# SCH_Genie-V1_2024-08-10.net
KiCad netlist of a schematic drawn in EasyEDA
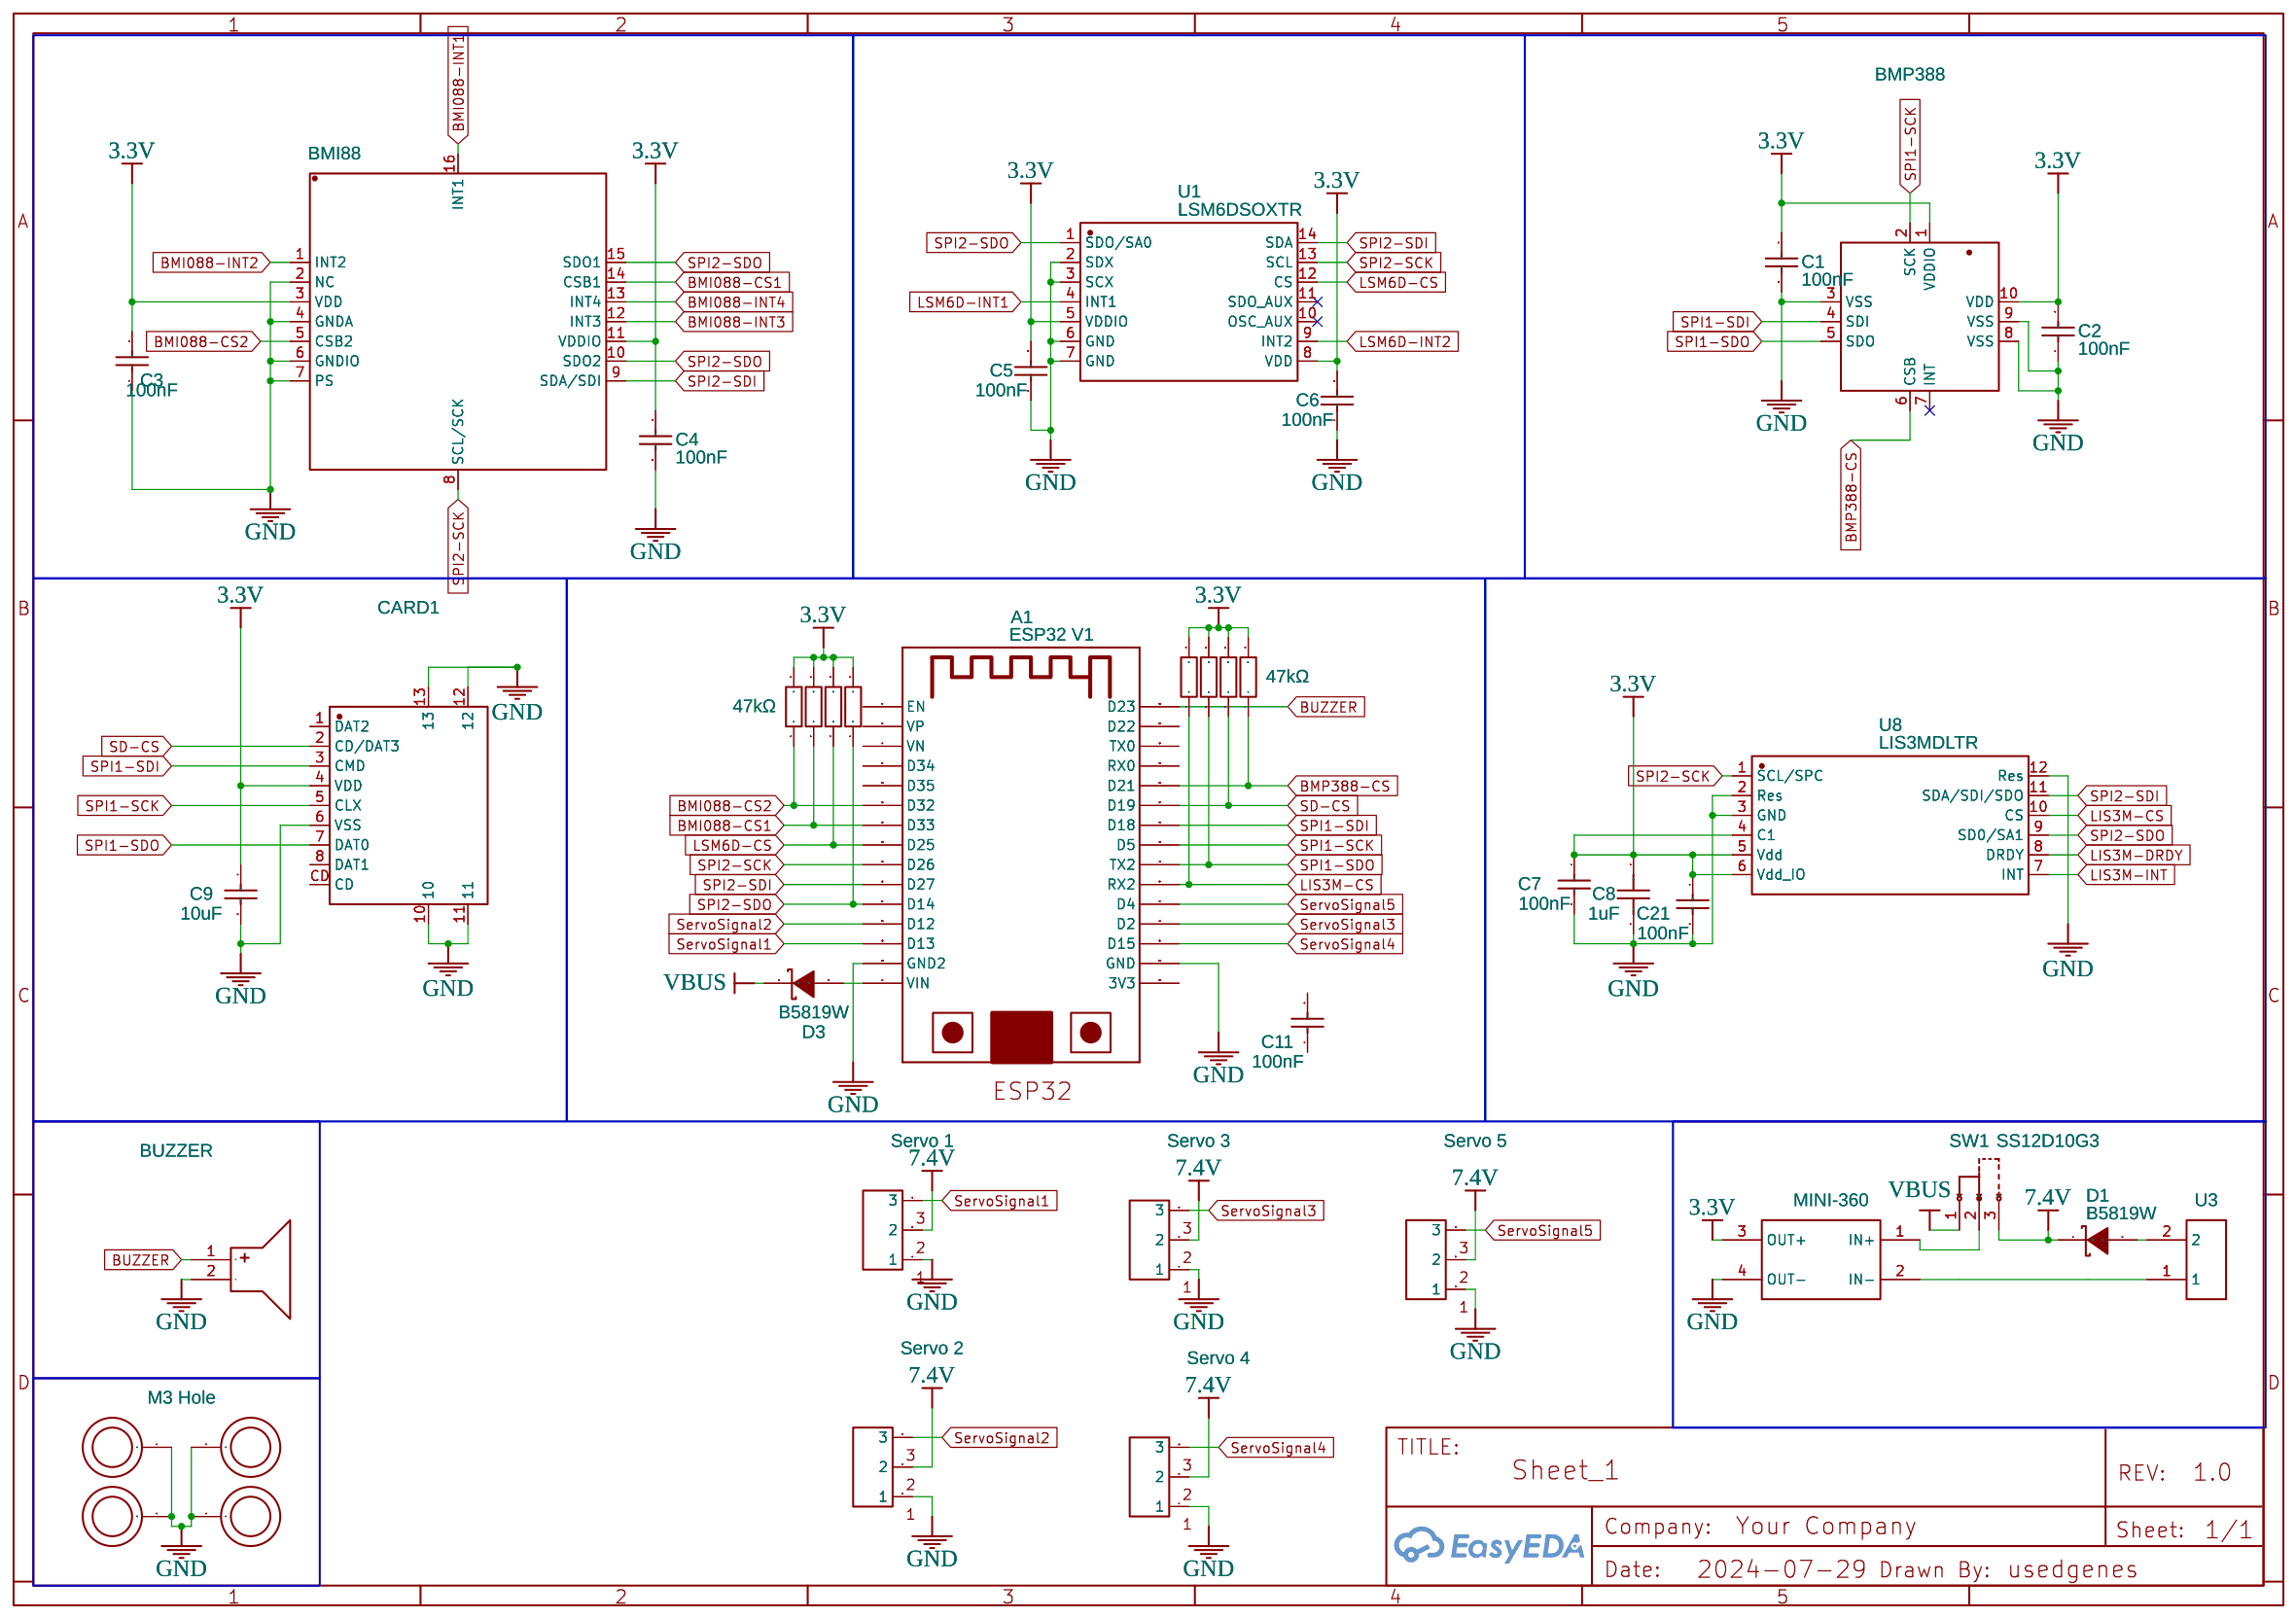
[diagram p0: schematic sheet]

(export (version "E")
  (design (tool "Eeschema 10.0.6"))
  (components
    (comp (ref "A1") (value "ESP32 V1") (libsource (lib "") (part "ESP32-DEVKIT-V1-30PIN")))
    (comp (ref "BMI88")
      (value "BMI088")
      (fields (field (name "Manufacturer") "Bosch(博世)"))
      (libsource (lib "") (part "BMI088"))
    )
    (comp (ref "BMP388")
      (value "BMP388")
      (fields (field (name "Manufacturer") "Bosch(博世)"))
      (libsource (lib "") (part "BMP388"))
    )
    (comp (ref "BUZZER")
      (value "4000Hz")
      (fields
        (field (name "Manufacturer Part") "SKY-1475-0540-45P7.6")
        (field (name "Manufacturer") "S&S(海旭)")
      )
      (libsource (lib "") (part "SKY-1475-0540-45P7.6"))
    )
    (comp (ref "C1")
      (value "100nF")
      (fields
        (field (name "Manufacturer Part") "CL05B104KO5NNNC")
        (field (name "Manufacturer") "SAMSUNG(三星)")
      )
      (libsource (lib "") (part "CL05B104KO5NNNC_1"))
    )
    (comp (ref "C2")
      (value "100nF")
      (fields
        (field (name "Manufacturer Part") "CL05B104KO5NNNC")
        (field (name "Manufacturer") "SAMSUNG(三星)")
      )
      (libsource (lib "") (part "CL05B104KO5NNNC_1"))
    )
    (comp (ref "C3")
      (value "100nF")
      (fields
        (field (name "Manufacturer Part") "CL05B104KO5NNNC")
        (field (name "Manufacturer") "SAMSUNG(三星)")
      )
      (libsource (lib "") (part "CL05B104KO5NNNC_1"))
    )
    (comp (ref "C4")
      (value "100nF")
      (fields
        (field (name "Manufacturer Part") "CL05B104KO5NNNC")
        (field (name "Manufacturer") "SAMSUNG(三星)")
      )
      (libsource (lib "") (part "CL05B104KO5NNNC_1"))
    )
    (comp (ref "C5")
      (value "100nF")
      (fields
        (field (name "Manufacturer Part") "CL05B104KO5NNNC")
        (field (name "Manufacturer") "SAMSUNG(三星)")
      )
      (libsource (lib "") (part "CL05B104KO5NNNC_1"))
    )
    (comp (ref "C6")
      (value "100nF")
      (fields
        (field (name "Manufacturer Part") "CL05B104KO5NNNC")
        (field (name "Manufacturer") "SAMSUNG(三星)")
      )
      (libsource (lib "") (part "CL05B104KO5NNNC_1"))
    )
    (comp (ref "C7")
      (value "100nF")
      (fields
        (field (name "Manufacturer Part") "CL05B104KO5NNNC")
        (field (name "Manufacturer") "SAMSUNG(三星)")
      )
      (libsource (lib "") (part "CL05B104KO5NNNC"))
    )
    (comp (ref "C8")
      (value "1uF")
      (fields
        (field (name "Manufacturer Part") "CL05A105KA5NQNC")
        (field (name "Manufacturer") "SAMSUNG(三星)")
      )
      (libsource (lib "") (part "CL05A105KA5NQNC"))
    )
    (comp (ref "C9")
      (value "10uF")
      (fields
        (field (name "Manufacturer Part") "CL05A106MQ5NUNC")
        (field (name "Manufacturer") "SAMSUNG(三星)")
      )
      (libsource (lib "") (part "CL05A106MQ5NUNC"))
    )
    (comp (ref "C11")
      (value "100nF")
      (fields
        (field (name "Manufacturer Part") "CL05B104KO5NNNC")
        (field (name "Manufacturer") "SAMSUNG(三星)")
      )
      (libsource (lib "") (part "CL05B104KO5NNNC_1"))
    )
    (comp (ref "C21")
      (value "100nF")
      (fields
        (field (name "Manufacturer Part") "CL05B104KO5NNNC")
        (field (name "Manufacturer") "SAMSUNG(三星)")
      )
      (libsource (lib "") (part "CL05B104KO5NNNC"))
    )
    (comp (ref "CARD1")
      (value "TF PUSH")
      (fields (field (name "Manufacturer") "SHOU HAN(首韩)"))
      (libsource (lib "") (part "TF PUSH"))
    )
    (comp (ref "D1")
      (value "B5819W")
      (fields (field (name "Manufacturer") "MDD(辰达半导体)"))
      (libsource (lib "") (part "B5819W"))
    )
    (comp (ref "D3")
      (value "B5819W")
      (fields (field (name "Manufacturer") "MDD(辰达半导体)"))
      (libsource (lib "") (part "B5819W"))
    )
    (comp (ref "H1") (value "M3 Hole") (libsource (lib "") (part "3MM_HOLE_1")))
    (comp (ref "H2") (value "3MM_HOLE") (libsource (lib "") (part "3MM_HOLE")))
    (comp (ref "H3") (value "3MM_HOLE") (libsource (lib "") (part "3MM_HOLE_1")))
    (comp (ref "H4") (value "3MM_HOLE") (libsource (lib "") (part "3MM_HOLE")))
    (comp (ref "MINI-360") (value "MINI-360") (libsource (lib "") (part "MINI-360")))
    (comp (ref "P1")
      (value "Servo 2")
      (fields
        (field (name "Manufacturer Part") "Female headerHDR1X8-2.54")
        (field (name "Manufacturer") "BOOMELE")
      )
      (libsource (lib "") (part "HEADER PAD 3X RMM COPY"))
    )
    (comp (ref "P2")
      (value "Servo 1")
      (fields
        (field (name "Manufacturer Part") "Female headerHDR1X8-2.54")
        (field (name "Manufacturer") "BOOMELE")
      )
      (libsource (lib "") (part "HEADER PAD 3X RMM COPY"))
    )
    (comp (ref "P3")
      (value "Servo 3")
      (fields
        (field (name "Manufacturer Part") "Female headerHDR1X8-2.54")
        (field (name "Manufacturer") "BOOMELE")
      )
      (libsource (lib "") (part "HEADER PAD 3X RMM COPY"))
    )
    (comp (ref "P4")
      (value "Servo 5")
      (fields
        (field (name "Manufacturer Part") "Female headerHDR1X8-2.54")
        (field (name "Manufacturer") "BOOMELE")
      )
      (libsource (lib "") (part "HEADER PAD 3X RMM COPY"))
    )
    (comp (ref "P5")
      (value "Servo 4")
      (fields
        (field (name "Manufacturer Part") "Female headerHDR1X8-2.54")
        (field (name "Manufacturer") "BOOMELE")
      )
      (libsource (lib "") (part "HEADER PAD 3X RMM COPY"))
    )
    (comp (ref "R1")
      (value "47kΩ")
      (fields
        (field (name "Manufacturer Part") "0402WGF4702TCE")
        (field (name "Manufacturer") "UNI-ROYAL(厚声)")
      )
      (libsource (lib "") (part "0402WGF4702TCE"))
    )
    (comp (ref "R2")
      (value "47kΩ")
      (fields
        (field (name "Manufacturer Part") "0402WGF4702TCE")
        (field (name "Manufacturer") "UNI-ROYAL(厚声)")
      )
      (libsource (lib "") (part "0402WGF4702TCE"))
    )
    (comp (ref "R3")
      (value "47kΩ")
      (fields
        (field (name "Manufacturer Part") "0402WGF4702TCE")
        (field (name "Manufacturer") "UNI-ROYAL(厚声)")
      )
      (libsource (lib "") (part "0402WGF4702TCE"))
    )
    (comp (ref "R4")
      (value "47kΩ")
      (fields
        (field (name "Manufacturer Part") "0402WGF4702TCE")
        (field (name "Manufacturer") "UNI-ROYAL(厚声)")
      )
      (libsource (lib "") (part "0402WGF4702TCE"))
    )
    (comp (ref "R5")
      (value "47kΩ")
      (fields
        (field (name "Manufacturer Part") "0402WGF4702TCE")
        (field (name "Manufacturer") "UNI-ROYAL(厚声)")
      )
      (libsource (lib "") (part "0402WGF4702TCE"))
    )
    (comp (ref "R7")
      (value "47kΩ")
      (fields
        (field (name "Manufacturer Part") "0402WGF4702TCE")
        (field (name "Manufacturer") "UNI-ROYAL(厚声)")
      )
      (libsource (lib "") (part "0402WGF4702TCE"))
    )
    (comp (ref "R8")
      (value "47kΩ")
      (fields
        (field (name "Manufacturer Part") "0402WGF4702TCE")
        (field (name "Manufacturer") "UNI-ROYAL(厚声)")
      )
      (libsource (lib "") (part "0402WGF4702TCE"))
    )
    (comp (ref "R9")
      (value "47kΩ")
      (fields
        (field (name "Manufacturer Part") "0402WGF4702TCE")
        (field (name "Manufacturer") "UNI-ROYAL(厚声)")
      )
      (libsource (lib "") (part "0402WGF4702TCE"))
    )
    (comp (ref "SW1")
      (value "SS12D10G3")
      (fields (field (name "Manufacturer") "SHOU HAN(首韩)"))
      (libsource (lib "") (part "SS12D10G3"))
    )
    (comp (ref "U1")
      (value "LSM6DSOXTR")
      (fields (field (name "Manufacturer") "ST(意法半导体)"))
      (libsource (lib "") (part "LSM6DSOXTR"))
    )
    (comp (ref "U3") (value "Power Pins") (libsource (lib "") (part "1X2")))
    (comp (ref "U8")
      (value "LIS3MDLTR")
      (fields (field (name "Manufacturer") "ST(意法半导体)"))
      (libsource (lib "") (part "LIS3MDLTR"))
    )
  )
  (nets
    (net (code "1") (name "3.3V") (class "Default")
      (node (ref "BMI88") (pin "11") (pinfunction "VDDIO_11") (pintype "unspecified"))
      (node (ref "BMI88") (pin "3") (pinfunction "VDD_3") (pintype "unspecified"))
      (node (ref "BMP388") (pin "1") (pinfunction "VDDIO_1") (pintype "unspecified"))
      (node (ref "BMP388") (pin "10") (pinfunction "VDD_10") (pintype "unspecified"))
      (node (ref "C1") (pin "2") (pinfunction "2_2") (pintype "input"))
      (node (ref "C2") (pin "2") (pinfunction "2_2") (pintype "input"))
      (node (ref "C21") (pin "1") (pinfunction "1_1") (pintype "input"))
      (node (ref "C3") (pin "2") (pinfunction "2_2") (pintype "input"))
      (node (ref "C4") (pin "2") (pinfunction "2_2") (pintype "input"))
      (node (ref "C5") (pin "2") (pinfunction "2_2") (pintype "input"))
      (node (ref "C6") (pin "2") (pinfunction "2_2") (pintype "input"))
      (node (ref "C7") (pin "1") (pinfunction "1_1") (pintype "input"))
      (node (ref "C8") (pin "2") (pinfunction "2_2") (pintype "unspecified"))
      (node (ref "C9") (pin "1") (pinfunction "1_1") (pintype "input"))
      (node (ref "CARD1") (pin "4") (pinfunction "VDD_4") (pintype "unspecified"))
      (node (ref "MINI-360") (pin "3") (pinfunction "OUT+_3") (pintype "unspecified"))
      (node (ref "R1") (pin "2") (pinfunction "2_2") (pintype "input"))
      (node (ref "R2") (pin "2") (pinfunction "2_2") (pintype "input"))
      (node (ref "R3") (pin "2") (pinfunction "2_2") (pintype "input"))
      (node (ref "R4") (pin "2") (pinfunction "2_2") (pintype "input"))
      (node (ref "R5") (pin "2") (pinfunction "2_2") (pintype "input"))
      (node (ref "R7") (pin "2") (pinfunction "2_2") (pintype "input"))
      (node (ref "R8") (pin "2") (pinfunction "2_2") (pintype "input"))
      (node (ref "R9") (pin "2") (pinfunction "2_2") (pintype "input"))
      (node (ref "U1") (pin "5") (pinfunction "VDDIO_5") (pintype "unspecified"))
      (node (ref "U1") (pin "8") (pinfunction "VDD_8") (pintype "unspecified"))
      (node (ref "U8") (pin "4") (pinfunction "C1_4") (pintype "unspecified"))
      (node (ref "U8") (pin "5") (pinfunction "Vdd_5") (pintype "unspecified"))
      (node (ref "U8") (pin "6") (pinfunction "Vdd_IO_6") (pintype "unspecified"))
    )
    (net (code "2") (name "7.4V") (class "Default")
      (node (ref "D1") (pin "1") (pinfunction "K_1") (pintype "unspecified"))
      (node (ref "P1") (pin "2") (pinfunction "2_2") (pintype "unspecified"))
      (node (ref "P2") (pin "2") (pinfunction "2_2") (pintype "unspecified"))
      (node (ref "P3") (pin "2") (pinfunction "2_2") (pintype "unspecified"))
      (node (ref "P4") (pin "2") (pinfunction "2_2") (pintype "unspecified"))
      (node (ref "P5") (pin "2") (pinfunction "2_2") (pintype "unspecified"))
      (node (ref "SW1") (pin "3") (pinfunction "3_3") (pintype "unspecified"))
    )
    (net (code "3") (name "BMI088-CS1") (class "Default")
      (node (ref "A1") (pin "D33") (pinfunction "D33_D33") (pintype "unspecified"))
      (node (ref "BMI88") (pin "14") (pinfunction "CSB1_14") (pintype "unspecified"))
      (node (ref "R1") (pin "1") (pinfunction "1_1") (pintype "input"))
    )
    (net (code "4") (name "BMI088-CS2") (class "Default")
      (node (ref "A1") (pin "D32") (pinfunction "D32_D32") (pintype "unspecified"))
      (node (ref "BMI88") (pin "5") (pinfunction "CSB2_5") (pintype "unspecified"))
      (node (ref "R4") (pin "1") (pinfunction "1_1") (pintype "input"))
    )
    (net (code "5") (name "BMI088-INT1") (class "Default")
      (node (ref "BMI88") (pin "16") (pinfunction "INT1_16") (pintype "unspecified"))
    )
    (net (code "6") (name "BMI088-INT2") (class "Default")
      (node (ref "BMI88") (pin "1") (pinfunction "INT2_1") (pintype "unspecified"))
    )
    (net (code "7") (name "BMI088-INT3") (class "Default")
      (node (ref "BMI88") (pin "12") (pinfunction "INT3_12") (pintype "unspecified"))
    )
    (net (code "8") (name "BMI088-INT4") (class "Default")
      (node (ref "BMI88") (pin "13") (pinfunction "INT4_13") (pintype "unspecified"))
    )
    (net (code "9") (name "BMP388-CS") (class "Default")
      (node (ref "A1") (pin "D21") (pinfunction "D21_D21") (pintype "unspecified"))
      (node (ref "BMP388") (pin "6") (pinfunction "CSB_6") (pintype "unspecified"))
      (node (ref "R5") (pin "1") (pinfunction "1_1") (pintype "input"))
    )
    (net (code "10") (name "BUZZER") (class "Default")
      (node (ref "A1") (pin "D23") (pinfunction "D23_D23") (pintype "unspecified"))
      (node (ref "BUZZER") (pin "1") (pinfunction "+_1") (pintype "unspecified"))
    )
    (net (code "11") (name "GND") (class "Default")
      (node (ref "A1") (pin "GND") (pinfunction "GND_GND") (pintype "unspecified"))
      (node (ref "A1") (pin "GND2") (pinfunction "GND2_GND2") (pintype "unspecified"))
      (node (ref "BMI88") (pin "2") (pinfunction "NC_2") (pintype "unspecified"))
      (node (ref "BMI88") (pin "4") (pinfunction "GNDA_4") (pintype "unspecified"))
      (node (ref "BMI88") (pin "6") (pinfunction "GNDIO_6") (pintype "unspecified"))
      (node (ref "BMI88") (pin "7") (pinfunction "PS_7") (pintype "unspecified"))
      (node (ref "BMP388") (pin "3") (pinfunction "VSS_3") (pintype "unspecified"))
      (node (ref "BMP388") (pin "8") (pinfunction "VSS_8") (pintype "unspecified"))
      (node (ref "BMP388") (pin "9") (pinfunction "VSS_9") (pintype "unspecified"))
      (node (ref "BUZZER") (pin "2") (pinfunction "-_2") (pintype "unspecified"))
      (node (ref "C1") (pin "1") (pinfunction "1_1") (pintype "input"))
      (node (ref "C2") (pin "1") (pinfunction "1_1") (pintype "input"))
      (node (ref "C21") (pin "2") (pinfunction "2_2") (pintype "input"))
      (node (ref "C3") (pin "1") (pinfunction "1_1") (pintype "input"))
      (node (ref "C4") (pin "1") (pinfunction "1_1") (pintype "input"))
      (node (ref "C5") (pin "1") (pinfunction "1_1") (pintype "input"))
      (node (ref "C6") (pin "1") (pinfunction "1_1") (pintype "input"))
      (node (ref "C7") (pin "2") (pinfunction "2_2") (pintype "input"))
      (node (ref "C8") (pin "1") (pinfunction "1_1") (pintype "unspecified"))
      (node (ref "C9") (pin "2") (pinfunction "2_2") (pintype "input"))
      (node (ref "CARD1") (pin "10") (pinfunction "10_10") (pintype "unspecified"))
      (node (ref "CARD1") (pin "11") (pinfunction "11_11") (pintype "unspecified"))
      (node (ref "CARD1") (pin "12") (pinfunction "12_12") (pintype "unspecified"))
      (node (ref "CARD1") (pin "13") (pinfunction "13_13") (pintype "unspecified"))
      (node (ref "CARD1") (pin "6") (pinfunction "VSS_6") (pintype "unspecified"))
      (node (ref "H1") (pin "1") (pinfunction "1_1") (pintype "bidirectional"))
      (node (ref "H2") (pin "1") (pinfunction "1_1") (pintype "bidirectional"))
      (node (ref "H3") (pin "1") (pinfunction "1_1") (pintype "bidirectional"))
      (node (ref "H4") (pin "1") (pinfunction "1_1") (pintype "bidirectional"))
      (node (ref "MINI-360") (pin "4") (pinfunction "OUT-_4") (pintype "unspecified"))
      (node (ref "P1") (pin "1") (pinfunction "1_1") (pintype "unspecified"))
      (node (ref "P2") (pin "1") (pinfunction "1_1") (pintype "unspecified"))
      (node (ref "P3") (pin "1") (pinfunction "1_1") (pintype "unspecified"))
      (node (ref "P4") (pin "1") (pinfunction "1_1") (pintype "unspecified"))
      (node (ref "P5") (pin "1") (pinfunction "1_1") (pintype "unspecified"))
      (node (ref "U1") (pin "2") (pinfunction "SDX_2") (pintype "unspecified"))
      (node (ref "U1") (pin "3") (pinfunction "SCX_3") (pintype "unspecified"))
      (node (ref "U1") (pin "6") (pinfunction "GND_6") (pintype "unspecified"))
      (node (ref "U1") (pin "7") (pinfunction "GND_7") (pintype "unspecified"))
      (node (ref "U8") (pin "12") (pinfunction "Res_12") (pintype "unspecified"))
      (node (ref "U8") (pin "2") (pinfunction "Res_2") (pintype "unspecified"))
      (node (ref "U8") (pin "3") (pinfunction "GND_3") (pintype "unspecified"))
    )
    (net (code "12") (name "LIS3M-CS") (class "Default")
      (node (ref "A1") (pin "RX2") (pinfunction "RX2_RX2") (pintype "unspecified"))
      (node (ref "R8") (pin "1") (pinfunction "1_1") (pintype "input"))
      (node (ref "U8") (pin "10") (pinfunction "CS_10") (pintype "unspecified"))
    )
    (net (code "13") (name "LIS3M-DRDY") (class "Default")
      (node (ref "U8") (pin "8") (pinfunction "DRDY_8") (pintype "unspecified"))
    )
    (net (code "14") (name "LIS3M-INT") (class "Default")
      (node (ref "U8") (pin "7") (pinfunction "INT_7") (pintype "unspecified"))
    )
    (net (code "15") (name "LSM6D-CS") (class "Default")
      (node (ref "A1") (pin "D25") (pinfunction "D25_D25") (pintype "unspecified"))
      (node (ref "R2") (pin "1") (pinfunction "1_1") (pintype "input"))
      (node (ref "U1") (pin "12") (pinfunction "CS_12") (pintype "unspecified"))
    )
    (net (code "16") (name "LSM6D-INT1") (class "Default")
      (node (ref "U1") (pin "4") (pinfunction "INT1_4") (pintype "unspecified"))
    )
    (net (code "17") (name "LSM6D-INT2") (class "Default")
      (node (ref "U1") (pin "9") (pinfunction "INT2_9") (pintype "unspecified"))
    )
    (net (code "18") (name "Net-(D1-A)") (class "Default")
      (node (ref "D1") (pin "2") (pinfunction "A_2") (pintype "unspecified"))
      (node (ref "U3") (pin "2") (pinfunction "2_2") (pintype "unspecified"))
    )
    (net (code "19") (name "Net-(D3-A)") (class "Default")
      (node (ref "A1") (pin "VIN") (pinfunction "VIN_VIN") (pintype "unspecified"))
      (node (ref "D3") (pin "2") (pinfunction "A_2") (pintype "unspecified"))
    )
    (net (code "20") (name "Net-(MINI-360-IN+)") (class "Default")
      (node (ref "MINI-360") (pin "1") (pinfunction "IN+_1") (pintype "unspecified"))
      (node (ref "SW1") (pin "2") (pinfunction "2_2") (pintype "unspecified"))
    )
    (net (code "21") (name "Net-(MINI-360-IN-)") (class "Default")
      (node (ref "MINI-360") (pin "2") (pinfunction "IN-_2") (pintype "unspecified"))
      (node (ref "U3") (pin "1") (pinfunction "1_1") (pintype "unspecified"))
    )
    (net (code "22") (name "SD-CS") (class "Default")
      (node (ref "A1") (pin "D19") (pinfunction "D19_D19") (pintype "unspecified"))
      (node (ref "CARD1") (pin "2") (pinfunction "CD/DAT3_2") (pintype "unspecified"))
      (node (ref "R7") (pin "1") (pinfunction "1_1") (pintype "input"))
    )
    (net (code "23") (name "SPI1-SCK") (class "Default")
      (node (ref "A1") (pin "D5") (pinfunction "D5_D5") (pintype "unspecified"))
      (node (ref "BMP388") (pin "2") (pinfunction "SCK_2") (pintype "unspecified"))
      (node (ref "CARD1") (pin "5") (pinfunction "CLX_5") (pintype "unspecified"))
    )
    (net (code "24") (name "SPI1-SDI") (class "Default")
      (node (ref "A1") (pin "D18") (pinfunction "D18_D18") (pintype "unspecified"))
      (node (ref "BMP388") (pin "4") (pinfunction "SDI_4") (pintype "unspecified"))
      (node (ref "CARD1") (pin "3") (pinfunction "CMD_3") (pintype "unspecified"))
    )
    (net (code "25") (name "SPI1-SDO") (class "Default")
      (node (ref "A1") (pin "TX2") (pinfunction "TX2_TX2") (pintype "unspecified"))
      (node (ref "BMP388") (pin "5") (pinfunction "SDO_5") (pintype "unspecified"))
      (node (ref "CARD1") (pin "7") (pinfunction "DAT0_7") (pintype "unspecified"))
      (node (ref "R9") (pin "1") (pinfunction "1_1") (pintype "input"))
    )
    (net (code "26") (name "SPI2-SCK") (class "Default")
      (node (ref "A1") (pin "D26") (pinfunction "D26_D26") (pintype "unspecified"))
      (node (ref "BMI88") (pin "8") (pinfunction "SCL/SCK_8") (pintype "unspecified"))
      (node (ref "U1") (pin "13") (pinfunction "SCL_13") (pintype "unspecified"))
      (node (ref "U8") (pin "1") (pinfunction "SCL/SPC_1") (pintype "unspecified"))
    )
    (net (code "27") (name "SPI2-SDI") (class "Default")
      (node (ref "A1") (pin "D27") (pinfunction "D27_D27") (pintype "unspecified"))
      (node (ref "BMI88") (pin "9") (pinfunction "SDA/SDI_9") (pintype "unspecified"))
      (node (ref "U1") (pin "14") (pinfunction "SDA_14") (pintype "unspecified"))
      (node (ref "U8") (pin "11") (pinfunction "SDA/SDI/SDO_11") (pintype "unspecified"))
    )
    (net (code "28") (name "SPI2-SDO") (class "Default")
      (node (ref "A1") (pin "D14") (pinfunction "D14_D14") (pintype "unspecified"))
      (node (ref "BMI88") (pin "10") (pinfunction "SDO2_10") (pintype "unspecified"))
      (node (ref "BMI88") (pin "15") (pinfunction "SDO1_15") (pintype "unspecified"))
      (node (ref "R3") (pin "1") (pinfunction "1_1") (pintype "input"))
      (node (ref "U1") (pin "1") (pinfunction "SDO/SA0_1") (pintype "unspecified"))
      (node (ref "U8") (pin "9") (pinfunction "SD0/SA1_9") (pintype "unspecified"))
    )
    (net (code "29") (name "ServoSignal1") (class "Default")
      (node (ref "A1") (pin "D13") (pinfunction "D13_D13") (pintype "unspecified"))
      (node (ref "P2") (pin "3") (pinfunction "3_3") (pintype "unspecified"))
    )
    (net (code "30") (name "ServoSignal2") (class "Default")
      (node (ref "A1") (pin "D12") (pinfunction "D12_D12") (pintype "unspecified"))
      (node (ref "P1") (pin "3") (pinfunction "3_3") (pintype "unspecified"))
    )
    (net (code "31") (name "ServoSignal3") (class "Default")
      (node (ref "A1") (pin "D2") (pinfunction "D2_D2") (pintype "unspecified"))
      (node (ref "P3") (pin "3") (pinfunction "3_3") (pintype "unspecified"))
    )
    (net (code "32") (name "ServoSignal4") (class "Default")
      (node (ref "A1") (pin "D15") (pinfunction "D15_D15") (pintype "unspecified"))
      (node (ref "P5") (pin "3") (pinfunction "3_3") (pintype "unspecified"))
    )
    (net (code "33") (name "ServoSignal5") (class "Default")
      (node (ref "A1") (pin "D4") (pinfunction "D4_D4") (pintype "unspecified"))
      (node (ref "P4") (pin "3") (pinfunction "3_3") (pintype "unspecified"))
    )
    (net (code "34") (name "VBUS") (class "Default")
      (node (ref "D3") (pin "1") (pinfunction "K_1") (pintype "unspecified"))
      (node (ref "SW1") (pin "1") (pinfunction "1_1") (pintype "unspecified"))
    )
    (net (code "35") (name "unconnected-(A1-Pad3V3)") (class "Default")
      (node (ref "A1") (pin "3V3") (pinfunction "3V3_3V3") (pintype "unspecified"))
    )
    (net (code "36") (name "unconnected-(A1-PadD22)") (class "Default")
      (node (ref "A1") (pin "D22") (pinfunction "D22_D22") (pintype "unspecified"))
    )
    (net (code "37") (name "unconnected-(A1-PadD34)") (class "Default")
      (node (ref "A1") (pin "D34") (pinfunction "D34_D34") (pintype "unspecified"))
    )
    (net (code "38") (name "unconnected-(A1-PadD35)") (class "Default")
      (node (ref "A1") (pin "D35") (pinfunction "D35_D35") (pintype "unspecified"))
    )
    (net (code "39") (name "unconnected-(A1-PadEN)") (class "Default")
      (node (ref "A1") (pin "EN") (pinfunction "EN_EN") (pintype "unspecified"))
    )
    (net (code "40") (name "unconnected-(A1-PadRX0)") (class "Default")
      (node (ref "A1") (pin "RX0") (pinfunction "RX0_RX0") (pintype "unspecified"))
    )
    (net (code "41") (name "unconnected-(A1-PadTX0)") (class "Default")
      (node (ref "A1") (pin "TX0") (pinfunction "TX0_TX0") (pintype "unspecified"))
    )
    (net (code "42") (name "unconnected-(A1-PadVN)") (class "Default")
      (node (ref "A1") (pin "VN") (pinfunction "VN_VN") (pintype "unspecified"))
    )
    (net (code "43") (name "unconnected-(A1-PadVP)") (class "Default")
      (node (ref "A1") (pin "VP") (pinfunction "VP_VP") (pintype "unspecified"))
    )
    (net (code "44") (name "unconnected-(BMP388-INT-Pad7)") (class "Default")
      (node (ref "BMP388") (pin "7") (pinfunction "INT_7") (pintype "unspecified+no_connect"))
    )
    (net (code "45") (name "unconnected-(C11-Pad1)") (class "Default")
      (node (ref "C11") (pin "1") (pinfunction "1_1") (pintype "input"))
    )
    (net (code "46") (name "unconnected-(C11-Pad2)") (class "Default")
      (node (ref "C11") (pin "2") (pinfunction "2_2") (pintype "input"))
    )
    (net (code "47") (name "unconnected-(CARD1-DAT1-Pad8)") (class "Default")
      (node (ref "CARD1") (pin "8") (pinfunction "DAT1_8") (pintype "unspecified"))
    )
    (net (code "48") (name "unconnected-(CARD1-DAT2-Pad1)") (class "Default")
      (node (ref "CARD1") (pin "1") (pinfunction "DAT2_1") (pintype "unspecified"))
    )
    (net (code "49") (name "unconnected-(CARD1-PadCD)") (class "Default")
      (node (ref "CARD1") (pin "CD") (pinfunction "CD_CD") (pintype "unspecified"))
    )
    (net (code "50") (name "unconnected-(U1-OSC_AUX-Pad10)") (class "Default")
      (node (ref "U1") (pin "10") (pinfunction "OSC_AUX_10") (pintype "unspecified+no_connect"))
    )
    (net (code "51") (name "unconnected-(U1-SDO_AUX-Pad11)") (class "Default")
      (node (ref "U1") (pin "11") (pinfunction "SDO_AUX_11") (pintype "unspecified+no_connect"))
    )
  )
)
